# ERpcukBOx.net
KiCad netlist of a schematic drawn in EAGLE
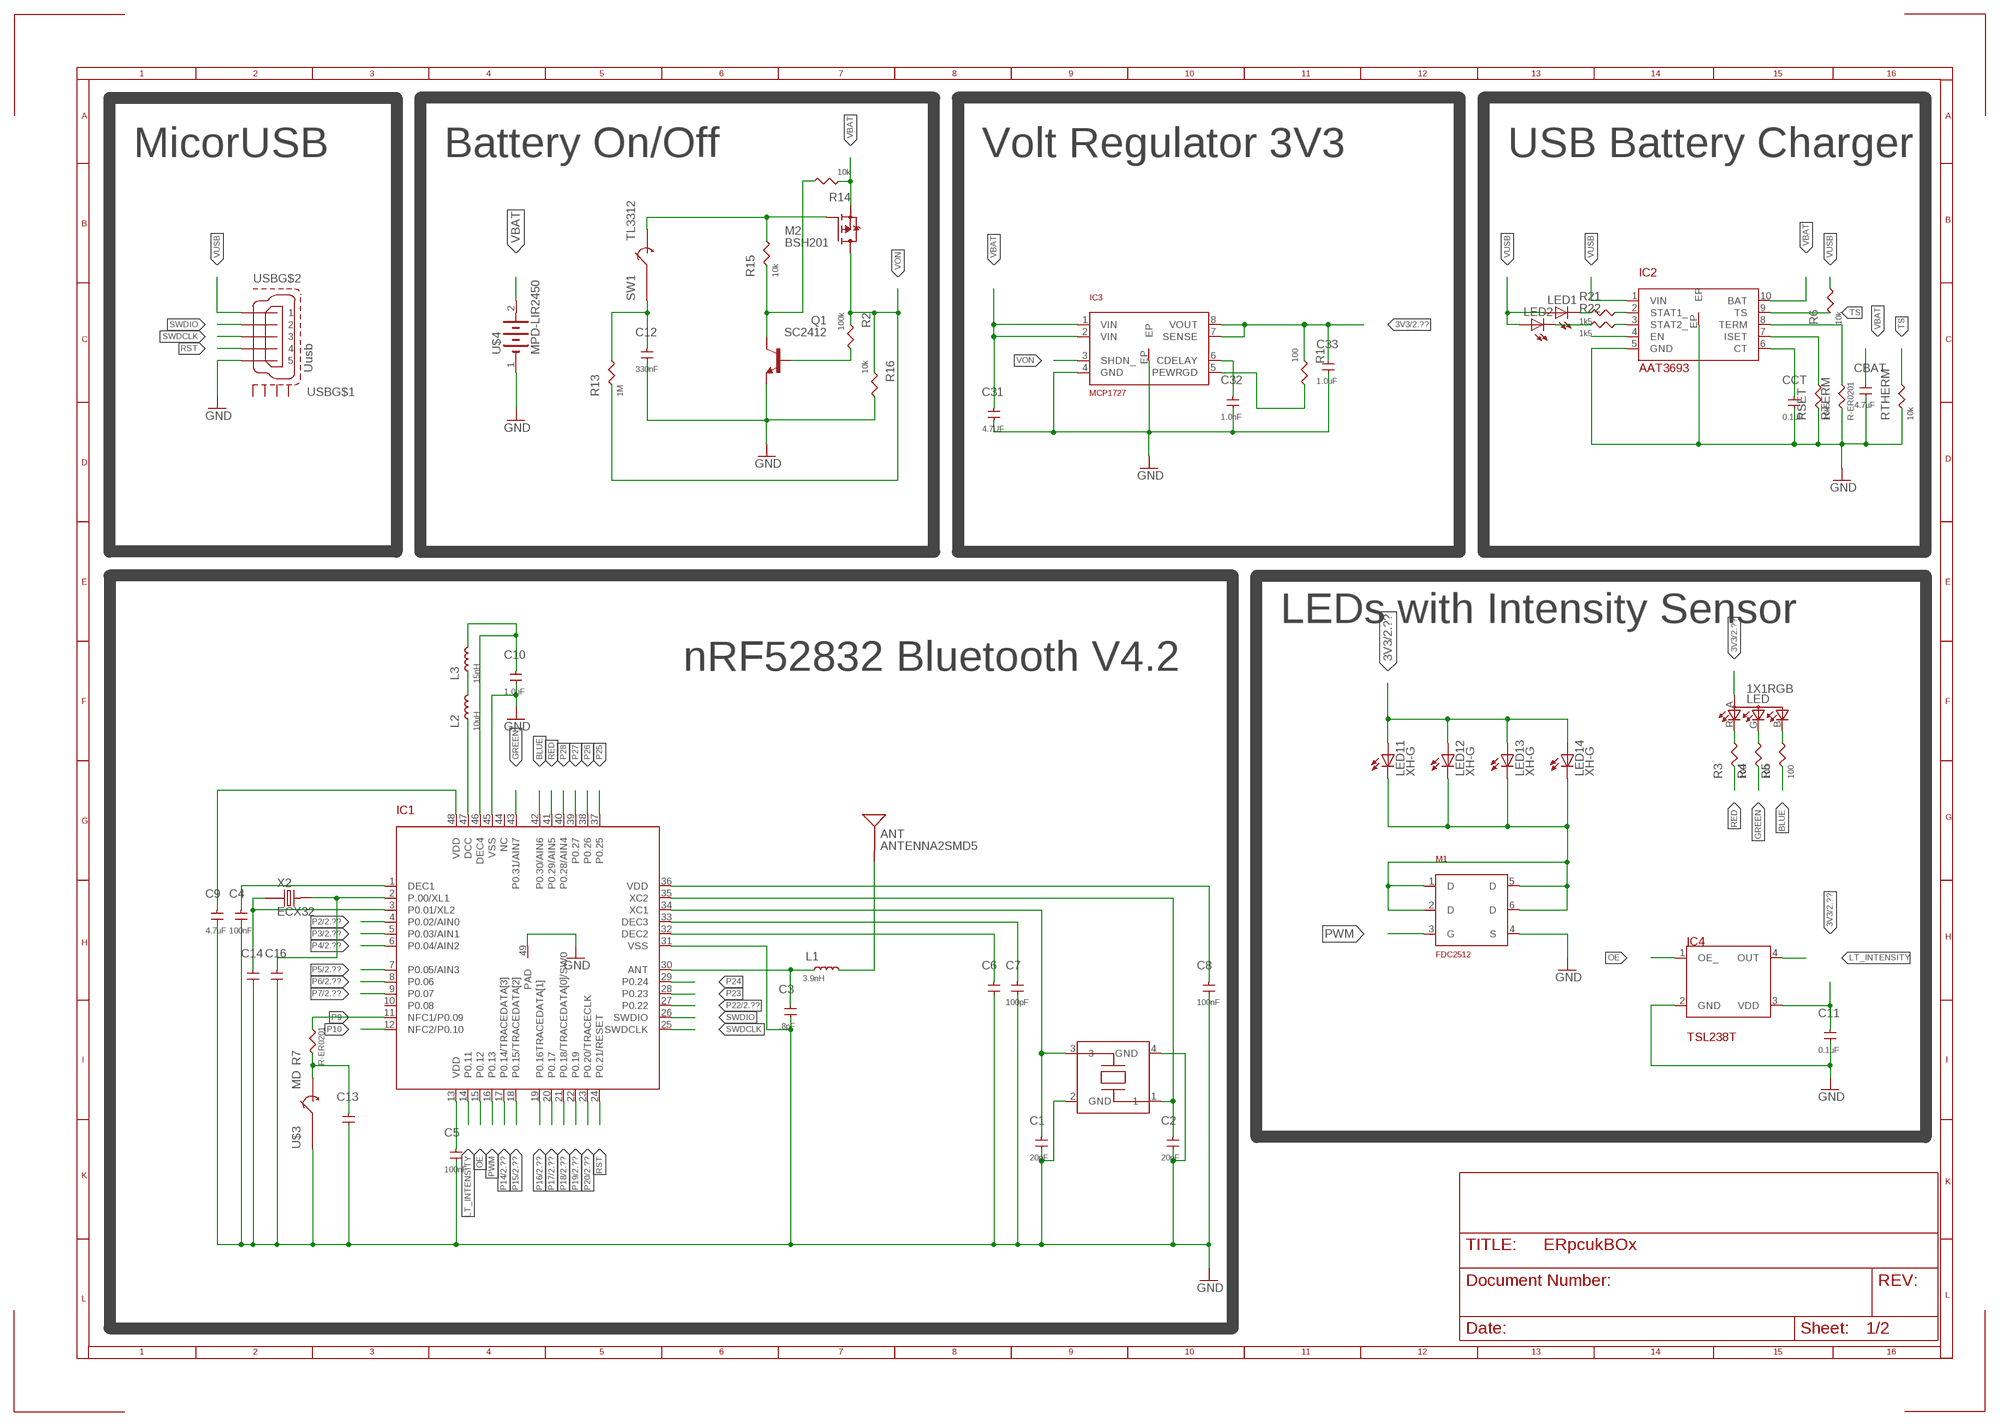
[diagram p0: schematic, sheet 1]
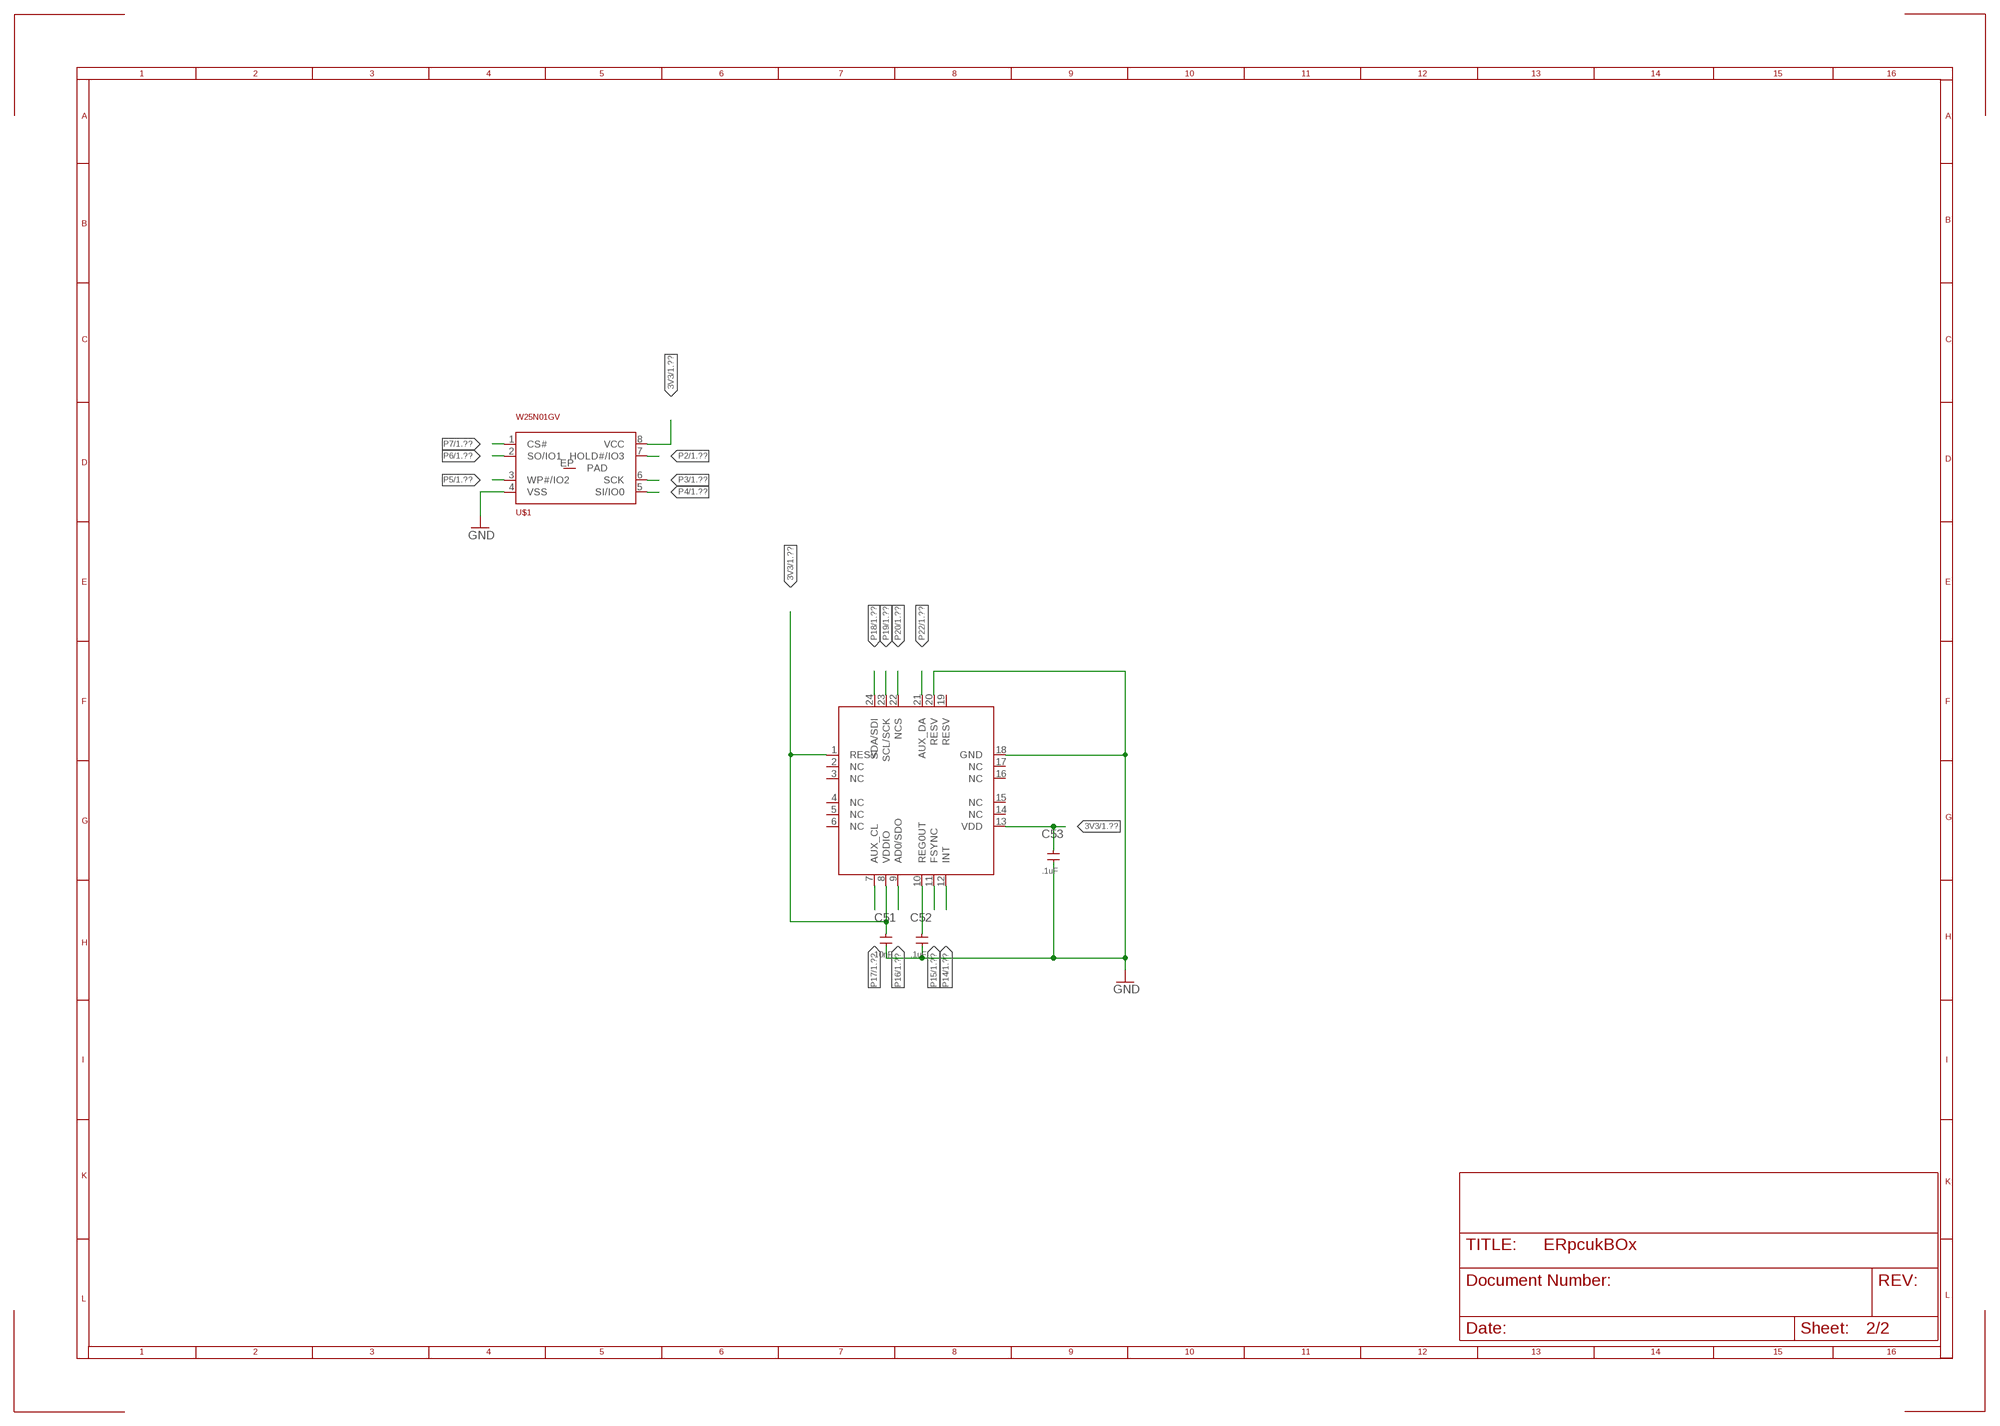
[diagram p1: schematic, sheet 2]

(export (version "E")
  (design (tool "Eeschema 10.0.6"))
  (components
    (comp (ref "C51")
      (value "10nF")
      (footprint "eagle-import:C0201")
      (libsource (lib "eagle-import") (part "C-ER201"))
    )
    (comp (ref "C52")
      (value ".1uF")
      (footprint "eagle-import:C0201")
      (libsource (lib "eagle-import") (part "C-ER201"))
    )
    (comp (ref "C53")
      (value ".1uF")
      (footprint "eagle-import:C0201")
      (libsource (lib "eagle-import") (part "C-ER201"))
    )
    (comp (ref "IC5")
      (value "MPU9250")
      (footprint "eagle-import:3X3_24_QFN_CORRECTED")
      (libsource (lib "eagle-import") (part "MPU9250_CORRECTED"))
    )
    (comp (ref "U$1")
      (value "W25N01GV")
      (footprint "eagle-import:8WSON6X8")
      (libsource (lib "eagle-import") (part "W25N01GV"))
    )
    (comp (ref "ANT")
      (value "ANTENNA2SMD5")
      (footprint "eagle-import:ANTENNA-CHIP5")
      (libsource (lib "eagle-import") (part "ANTENNA2SMD5"))
    )
    (comp (ref "C1")
      (value "20pF")
      (footprint "eagle-import:C0201")
      (libsource (lib "eagle-import") (part "C-ER201"))
    )
    (comp (ref "C2")
      (value "20pF")
      (footprint "eagle-import:C0201")
      (libsource (lib "eagle-import") (part "C-ER201"))
    )
    (comp (ref "C3")
      (value ".8pF")
      (footprint "eagle-import:C0201")
      (libsource (lib "eagle-import") (part "C-ER201"))
    )
    (comp (ref "C4")
      (value "100nF")
      (footprint "eagle-import:C0201")
      (libsource (lib "eagle-import") (part "C-ER201"))
    )
    (comp (ref "C5")
      (value "100nF")
      (footprint "eagle-import:C0201")
      (libsource (lib "eagle-import") (part "C-ER201"))
    )
    (comp (ref "C6")
      (value "C-ER201")
      (footprint "eagle-import:C0201")
      (libsource (lib "eagle-import") (part "C-ER201"))
    )
    (comp (ref "C7")
      (value "100pF")
      (footprint "eagle-import:C0201")
      (libsource (lib "eagle-import") (part "C-ER201"))
    )
    (comp (ref "C8")
      (value "100nF")
      (footprint "eagle-import:C0201")
      (libsource (lib "eagle-import") (part "C-ER201"))
    )
    (comp (ref "C9")
      (value "4.7uF")
      (footprint "eagle-import:C0402")
      (libsource (lib "eagle-import") (part "C-ERC0402"))
    )
    (comp (ref "C10")
      (value "1.0uF")
      (footprint "eagle-import:C0201")
      (libsource (lib "eagle-import") (part "C-ER201"))
    )
    (comp (ref "C11")
      (value "0.1uF")
      (footprint "eagle-import:C0201")
      (libsource (lib "eagle-import") (part "C-ER201"))
    )
    (comp (ref "C12")
      (value "330nF")
      (footprint "eagle-import:C0201")
      (libsource (lib "eagle-import") (part "C-ER201"))
    )
    (comp (ref "C13")
      (value "C-ER201")
      (footprint "eagle-import:C0201")
      (libsource (lib "eagle-import") (part "C-ER201"))
    )
    (comp (ref "C14")
      (value "C-ER201")
      (footprint "eagle-import:C0201")
      (libsource (lib "eagle-import") (part "C-ER201"))
    )
    (comp (ref "C16")
      (value "C-ER201")
      (footprint "eagle-import:C0201")
      (libsource (lib "eagle-import") (part "C-ER201"))
    )
    (comp (ref "C31")
      (value "4.7UF")
      (footprint "eagle-import:C0402")
      (libsource (lib "eagle-import") (part "C-ERC0402"))
    )
    (comp (ref "C32")
      (value "1.0nF")
      (footprint "eagle-import:C0201")
      (libsource (lib "eagle-import") (part "C-ER201"))
    )
    (comp (ref "C33")
      (value "1.0uF")
      (footprint "eagle-import:C0201")
      (libsource (lib "eagle-import") (part "C-ER201"))
    )
    (comp (ref "CBAT")
      (value "4.7uF")
      (footprint "eagle-import:C0402")
      (libsource (lib "eagle-import") (part "C-ERC0402"))
    )
    (comp (ref "CCT")
      (value "0.1uF")
      (footprint "eagle-import:C0201")
      (libsource (lib "eagle-import") (part "C-ER201"))
    )
    (comp (ref "IC1")
      (value "NRF52832")
      (footprint "eagle-import:QFN48")
      (libsource (lib "eagle-import") (part "NRF52832"))
    )
    (comp (ref "IC2")
      (value "AAT3693")
      (footprint "eagle-import:AAT3693")
      (libsource (lib "eagle-import") (part "AAT3693"))
    )
    (comp (ref "IC3")
      (value "MCP1727")
      (footprint "eagle-import:DFN8-3X3")
      (libsource (lib "eagle-import") (part "MCP1727"))
    )
    (comp (ref "IC4")
      (value "TSL238T")
      (footprint "eagle-import:T4")
      (libsource (lib "eagle-import") (part "TSL238T"))
    )
    (comp (ref "L1")
      (value "3.9nH")
      (footprint "eagle-import:C0201")
      (libsource (lib "eagle-import") (part "L-ER0201"))
    )
    (comp (ref "L2")
      (value "10uH")
      (footprint "eagle-import:R0603")
      (libsource (lib "eagle-import") (part "L-ERL603"))
    )
    (comp (ref "L3")
      (value "15nH")
      (footprint "eagle-import:C0201")
      (libsource (lib "eagle-import") (part "L-ER0201"))
    )
    (comp (ref "LED")
      (value "1X1RGB")
      (footprint "eagle-import:1X1")
      (libsource (lib "eagle-import") (part "1X1RGB"))
    )
    (comp (ref "LED1")
      (value "LEDCHIP-LED0603")
      (footprint "eagle-import:CHIP-LED0603")
      (libsource (lib "eagle-import") (part "LEDCHIP-LED0603"))
    )
    (comp (ref "LED2")
      (value "LEDCHIP-LED0603")
      (footprint "eagle-import:CHIP-LED0603")
      (libsource (lib "eagle-import") (part "LEDCHIP-LED0603"))
    )
    (comp (ref "LED11")
      (value "XH-G")
      (footprint "eagle-import:XH-G")
      (libsource (lib "eagle-import") (part "XH-G"))
    )
    (comp (ref "LED12")
      (value "XH-G")
      (footprint "eagle-import:XH-G")
      (libsource (lib "eagle-import") (part "XH-G"))
    )
    (comp (ref "LED13")
      (value "XH-G")
      (footprint "eagle-import:XH-G")
      (libsource (lib "eagle-import") (part "XH-G"))
    )
    (comp (ref "LED14")
      (value "XH-G")
      (footprint "eagle-import:XH-G")
      (libsource (lib "eagle-import") (part "XH-G"))
    )
    (comp (ref "M1")
      (value "FDC2512")
      (footprint "eagle-import:SSOT6")
      (libsource (lib "eagle-import") (part "FDC2512"))
    )
    (comp (ref "M2")
      (value "BSH201")
      (footprint "eagle-import:SOT23")
      (libsource (lib "eagle-import") (part "BSH201"))
    )
    (comp (ref "Q1")
      (value "SC2412")
      (footprint "eagle-import:SC59-BEC")
      (libsource (lib "eagle-import") (part "SC2412"))
    )
    (comp (ref "R1")
      (value "100")
      (footprint "eagle-import:R0201")
      (libsource (lib "eagle-import") (part "R-ER0201"))
    )
    (comp (ref "R2")
      (value "100k")
      (footprint "eagle-import:R0201")
      (libsource (lib "eagle-import") (part "R-ER0201"))
    )
    (comp (ref "R3")
      (value "100")
      (footprint "eagle-import:R0201")
      (libsource (lib "eagle-import") (part "R-ER0201"))
    )
    (comp (ref "R4")
      (value "100")
      (footprint "eagle-import:R0201")
      (libsource (lib "eagle-import") (part "R-ER0201"))
    )
    (comp (ref "R5")
      (value "100")
      (footprint "eagle-import:R0201")
      (libsource (lib "eagle-import") (part "R-ER0201"))
    )
    (comp (ref "R6")
      (value "10k")
      (footprint "eagle-import:R0201")
      (libsource (lib "eagle-import") (part "R-ER0201"))
    )
    (comp (ref "R7")
      (value "R-ER0201")
      (footprint "eagle-import:R0201")
      (libsource (lib "eagle-import") (part "R-ER0201"))
    )
    (comp (ref "R13")
      (value "1M")
      (footprint "eagle-import:R0201")
      (libsource (lib "eagle-import") (part "R-ER0201"))
    )
    (comp (ref "R14")
      (value "10k")
      (footprint "eagle-import:R0201")
      (libsource (lib "eagle-import") (part "R-ER0201"))
    )
    (comp (ref "R15")
      (value "10k")
      (footprint "eagle-import:R0201")
      (libsource (lib "eagle-import") (part "R-ER0201"))
    )
    (comp (ref "R16")
      (value "10k")
      (footprint "eagle-import:R0201")
      (libsource (lib "eagle-import") (part "R-ER0201"))
    )
    (comp (ref "R21")
      (value "1k5")
      (footprint "eagle-import:R0201")
      (libsource (lib "eagle-import") (part "R-ER0201"))
    )
    (comp (ref "R22")
      (value "1k5")
      (footprint "eagle-import:R0201")
      (libsource (lib "eagle-import") (part "R-ER0201"))
    )
    (comp (ref "RSET")
      (value "16k5")
      (footprint "eagle-import:R0201")
      (libsource (lib "eagle-import") (part "R-ER0201"))
    )
    (comp (ref "RTERM")
      (value "R-ER0201")
      (footprint "eagle-import:R0201")
      (libsource (lib "eagle-import") (part "R-ER0201"))
    )
    (comp (ref "RTHERM")
      (value "10k")
      (footprint "eagle-import:R0201")
      (libsource (lib "eagle-import") (part "R-ER0201"))
    )
    (comp (ref "SW1")
      (value "TL3312")
      (footprint "eagle-import:TL3312")
      (libsource (lib "eagle-import") (part "TL3312"))
    )
    (comp (ref "U$3") (value "MD") (footprint "eagle-import:MD") (libsource (lib "eagle-import") (part "MD")))
    (comp (ref "U$4")
      (value "MPD-LIR2450")
      (footprint "eagle-import:LIR2450")
      (libsource (lib "eagle-import") (part "MPD-LIR2450"))
    )
    (comp (ref "USB")
      (value "Uusb")
      (footprint "eagle-import:ZX62R-B-5P")
      (libsource (lib "eagle-import") (part "MICRO-USB-SHIELD-ZX62R-B-5P"))
    )
    (comp (ref "X1")
      (value "FA-128")
      (footprint "eagle-import:FA-128")
      (libsource (lib "eagle-import") (part "FA-128"))
    )
    (comp (ref "X2")
      (value "ECX32")
      (footprint "eagle-import:ECX39")
      (libsource (lib "eagle-import") (part "ECX32"))
    )
  )
  (nets
    (net (code "1") (name "3V3") (class "Default")
      (node (ref "C11") (pin "2") (pinfunction "P$2_2") (pintype "bidirectional"))
      (node (ref "C33") (pin "2") (pinfunction "P$2_2") (pintype "bidirectional"))
      (node (ref "C5") (pin "2") (pinfunction "P$2_2") (pintype "bidirectional"))
      (node (ref "C51") (pin "2") (pinfunction "P$2_2") (pintype "bidirectional"))
      (node (ref "C53") (pin "2") (pinfunction "P$2_2") (pintype "bidirectional"))
      (node (ref "C8") (pin "2") (pinfunction "P$2_2") (pintype "bidirectional"))
      (node (ref "C9") (pin "2") (pinfunction "P$2_2") (pintype "bidirectional"))
      (node (ref "IC1") (pin "13") (pinfunction "VDD_13") (pintype "bidirectional"))
      (node (ref "IC1") (pin "36") (pinfunction "VDD_36") (pintype "bidirectional"))
      (node (ref "IC1") (pin "48") (pinfunction "VDD_48") (pintype "bidirectional"))
      (node (ref "IC3") (pin "7") (pinfunction "SENSE_7") (pintype "bidirectional"))
      (node (ref "IC3") (pin "8") (pinfunction "VOUT_8") (pintype "bidirectional"))
      (node (ref "IC4") (pin "3") (pinfunction "VDD_3") (pintype "bidirectional"))
      (node (ref "IC5") (pin "1") (pinfunction "RESV_1") (pintype "bidirectional"))
      (node (ref "IC5") (pin "13") (pinfunction "VDD_13") (pintype "bidirectional"))
      (node (ref "IC5") (pin "8") (pinfunction "VDDIO_8") (pintype "bidirectional"))
      (node (ref "LED") (pin "A") (pinfunction "A2_A") (pintype "passive"))
      (node (ref "LED11") (pin "2") (pinfunction "A_2") (pintype "passive"))
      (node (ref "LED12") (pin "2") (pinfunction "A_2") (pintype "passive"))
      (node (ref "LED13") (pin "2") (pinfunction "A_2") (pintype "passive"))
      (node (ref "LED14") (pin "2") (pinfunction "A_2") (pintype "passive"))
      (node (ref "R1") (pin "1") (pinfunction "P$1_1") (pintype "bidirectional"))
      (node (ref "U$1") (pin "8") (pinfunction "VCC_8") (pintype "bidirectional"))
    )
    (net (code "2") (name "BLUE") (class "Default")
      (node (ref "IC1") (pin "42") (pinfunction "P0.30/AIN6_42") (pintype "bidirectional"))
      (node (ref "R5") (pin "1") (pinfunction "P$1_1") (pintype "bidirectional"))
    )
    (net (code "3") (name "GND") (class "Default")
      (node (ref "C1") (pin "1") (pinfunction "P$1_1") (pintype "bidirectional"))
      (node (ref "C10") (pin "1") (pinfunction "P$1_1") (pintype "bidirectional"))
      (node (ref "C11") (pin "1") (pinfunction "P$1_1") (pintype "bidirectional"))
      (node (ref "C12") (pin "1") (pinfunction "P$1_1") (pintype "bidirectional"))
      (node (ref "C13") (pin "1") (pinfunction "P$1_1") (pintype "bidirectional"))
      (node (ref "C14") (pin "1") (pinfunction "P$1_1") (pintype "bidirectional"))
      (node (ref "C16") (pin "1") (pinfunction "P$1_1") (pintype "bidirectional"))
      (node (ref "C2") (pin "1") (pinfunction "P$1_1") (pintype "bidirectional"))
      (node (ref "C3") (pin "1") (pinfunction "P$1_1") (pintype "bidirectional"))
      (node (ref "C31") (pin "1") (pinfunction "P$1_1") (pintype "bidirectional"))
      (node (ref "C32") (pin "1") (pinfunction "P$1_1") (pintype "bidirectional"))
      (node (ref "C33") (pin "1") (pinfunction "P$1_1") (pintype "bidirectional"))
      (node (ref "C4") (pin "1") (pinfunction "P$1_1") (pintype "bidirectional"))
      (node (ref "C5") (pin "1") (pinfunction "P$1_1") (pintype "bidirectional"))
      (node (ref "C51") (pin "1") (pinfunction "P$1_1") (pintype "bidirectional"))
      (node (ref "C52") (pin "1") (pinfunction "P$1_1") (pintype "bidirectional"))
      (node (ref "C53") (pin "1") (pinfunction "P$1_1") (pintype "bidirectional"))
      (node (ref "C6") (pin "1") (pinfunction "P$1_1") (pintype "bidirectional"))
      (node (ref "C7") (pin "1") (pinfunction "P$1_1") (pintype "bidirectional"))
      (node (ref "C8") (pin "1") (pinfunction "P$1_1") (pintype "bidirectional"))
      (node (ref "C9") (pin "1") (pinfunction "P$1_1") (pintype "bidirectional"))
      (node (ref "CBAT") (pin "1") (pinfunction "P$1_1") (pintype "bidirectional"))
      (node (ref "CCT") (pin "1") (pinfunction "P$1_1") (pintype "bidirectional"))
      (node (ref "IC1") (pin "31") (pinfunction "VSS_31") (pintype "bidirectional"))
      (node (ref "IC1") (pin "45") (pinfunction "VSS_45") (pintype "bidirectional"))
      (node (ref "IC1") (pin "49") (pinfunction "PAD_49") (pintype "bidirectional"))
      (node (ref "IC2") (pin "5") (pinfunction "GND_5") (pintype "bidirectional"))
      (node (ref "IC2") (pin "EP") (pinfunction "EP_EP") (pintype "bidirectional"))
      (node (ref "IC3") (pin "4") (pinfunction "GND_4") (pintype "bidirectional"))
      (node (ref "IC3") (pin "EP") (pinfunction "EP_EP") (pintype "bidirectional"))
      (node (ref "IC4") (pin "2") (pinfunction "GND_2") (pintype "bidirectional"))
      (node (ref "IC5") (pin "18") (pinfunction "GND_18") (pintype "bidirectional"))
      (node (ref "IC5") (pin "20") (pinfunction "RESV_20") (pintype "bidirectional"))
      (node (ref "M1") (pin "4") (pinfunction "S_4") (pintype "bidirectional"))
      (node (ref "Q1") (pin "E") (pinfunction "E_E") (pintype "passive"))
      (node (ref "R16") (pin "2") (pinfunction "P$2_2") (pintype "bidirectional"))
      (node (ref "RSET") (pin "1") (pinfunction "P$1_1") (pintype "bidirectional"))
      (node (ref "RTERM") (pin "1") (pinfunction "P$1_1") (pintype "bidirectional"))
      (node (ref "RTHERM") (pin "1") (pinfunction "P$1_1") (pintype "bidirectional"))
      (node (ref "U$1") (pin "4") (pinfunction "VSS_4") (pintype "bidirectional"))
      (node (ref "U$3") (pin "P$1") (pinfunction "1_P$1") (pintype "bidirectional"))
      (node (ref "U$4") (pin "1") (pinfunction "-_1") (pintype "passive"))
      (node (ref "USB") (pin "1") (pinfunction "5_1") (pintype "input"))
      (node (ref "X1") (pin "2") (pinfunction "GND_2") (pintype "bidirectional"))
      (node (ref "X1") (pin "4") (pinfunction "GND_4") (pintype "bidirectional"))
    )
    (net (code "4") (name "GREEN") (class "Default")
      (node (ref "IC1") (pin "43") (pinfunction "P0.31/AIN7_43") (pintype "bidirectional"))
      (node (ref "R4") (pin "1") (pinfunction "P$1_1") (pintype "bidirectional"))
    )
    (net (code "5") (name "LT_INTENSITY") (class "Default")
      (node (ref "IC1") (pin "14") (pinfunction "P0.11_14") (pintype "bidirectional"))
      (node (ref "IC4") (pin "4") (pinfunction "OUT_4") (pintype "bidirectional"))
    )
    (net (code "6") (name "Net-(ANT-SIGNAL)") (class "Default")
      (node (ref "ANT") (pin "FEED") (pinfunction "SIGNAL_FEED") (pintype "bidirectional"))
      (node (ref "L1") (pin "2") (pinfunction "P$2_2") (pintype "bidirectional"))
    )
    (net (code "7") (name "Net-(C1-P$2)") (class "Default")
      (node (ref "C1") (pin "2") (pinfunction "P$2_2") (pintype "bidirectional"))
      (node (ref "IC1") (pin "34") (pinfunction "XC1_34") (pintype "bidirectional"))
      (node (ref "X1") (pin "3") (pinfunction "3_3") (pintype "bidirectional"))
    )
    (net (code "8") (name "Net-(C2-P$2)") (class "Default")
      (node (ref "C2") (pin "2") (pinfunction "P$2_2") (pintype "bidirectional"))
      (node (ref "IC1") (pin "35") (pinfunction "XC2_35") (pintype "bidirectional"))
      (node (ref "X1") (pin "1") (pinfunction "1_1") (pintype "bidirectional"))
    )
    (net (code "9") (name "Net-(C3-P$2)") (class "Default")
      (node (ref "C3") (pin "2") (pinfunction "P$2_2") (pintype "bidirectional"))
      (node (ref "IC1") (pin "30") (pinfunction "ANT_30") (pintype "bidirectional"))
      (node (ref "L1") (pin "1") (pinfunction "P$1_1") (pintype "bidirectional"))
    )
    (net (code "10") (name "Net-(C4-P$2)") (class "Default")
      (node (ref "C4") (pin "2") (pinfunction "P$2_2") (pintype "bidirectional"))
      (node (ref "IC1") (pin "1") (pinfunction "DEC1_1") (pintype "bidirectional"))
    )
    (net (code "11") (name "Net-(C6-P$2)") (class "Default")
      (node (ref "C6") (pin "2") (pinfunction "P$2_2") (pintype "bidirectional"))
      (node (ref "IC1") (pin "32") (pinfunction "DEC2_32") (pintype "bidirectional"))
    )
    (net (code "12") (name "Net-(C7-P$2)") (class "Default")
      (node (ref "C7") (pin "2") (pinfunction "P$2_2") (pintype "bidirectional"))
      (node (ref "IC1") (pin "33") (pinfunction "DEC3_33") (pintype "bidirectional"))
    )
    (net (code "13") (name "Net-(C10-P$2)") (class "Default")
      (node (ref "C10") (pin "2") (pinfunction "P$2_2") (pintype "bidirectional"))
      (node (ref "IC1") (pin "46") (pinfunction "DEC4_46") (pintype "bidirectional"))
      (node (ref "L3") (pin "2") (pinfunction "P$2_2") (pintype "bidirectional"))
    )
    (net (code "14") (name "Net-(C12-P$2)") (class "Default")
      (node (ref "C12") (pin "2") (pinfunction "P$2_2") (pintype "bidirectional"))
      (node (ref "R13") (pin "2") (pinfunction "P$2_2") (pintype "bidirectional"))
      (node (ref "SW1") (pin "1") (pinfunction "1_1") (pintype "bidirectional"))
    )
    (net (code "15") (name "Net-(C13-P$2)") (class "Default")
      (node (ref "C13") (pin "2") (pinfunction "P$2_2") (pintype "bidirectional"))
      (node (ref "R7") (pin "1") (pinfunction "P$1_1") (pintype "bidirectional"))
      (node (ref "U$3") (pin "P$2") (pinfunction "2_P$2") (pintype "bidirectional"))
    )
    (net (code "16") (name "Net-(C14-P$2)") (class "Default")
      (node (ref "C14") (pin "2") (pinfunction "P$2_2") (pintype "bidirectional"))
      (node (ref "IC1") (pin "3") (pinfunction "P0.01/XL2_3") (pintype "bidirectional"))
      (node (ref "X2") (pin "P$1") (pinfunction "1_P$1") (pintype "passive"))
    )
    (net (code "17") (name "Net-(C16-P$2)") (class "Default")
      (node (ref "C16") (pin "2") (pinfunction "P$2_2") (pintype "bidirectional"))
      (node (ref "IC1") (pin "2") (pinfunction "P.00/XL1_2") (pintype "bidirectional"))
      (node (ref "X2") (pin "P$2") (pinfunction "2_P$2") (pintype "passive"))
    )
    (net (code "18") (name "Net-(C32-P$2)") (class "Default")
      (node (ref "C32") (pin "2") (pinfunction "P$2_2") (pintype "bidirectional"))
      (node (ref "IC3") (pin "6") (pinfunction "CDELAY_6") (pintype "bidirectional"))
    )
    (net (code "19") (name "Net-(C52-P$2)") (class "Default")
      (node (ref "C52") (pin "2") (pinfunction "P$2_2") (pintype "bidirectional"))
      (node (ref "IC5") (pin "10") (pinfunction "REG0UT_10") (pintype "bidirectional"))
    )
    (net (code "20") (name "Net-(CCT-P$2)") (class "Default")
      (node (ref "CCT") (pin "2") (pinfunction "P$2_2") (pintype "bidirectional"))
      (node (ref "IC2") (pin "6") (pinfunction "CT_6") (pintype "bidirectional"))
    )
    (net (code "21") (name "Net-(IC1-DCC)") (class "Default")
      (node (ref "IC1") (pin "47") (pinfunction "DCC_47") (pintype "bidirectional"))
      (node (ref "L2") (pin "1") (pinfunction "P$1_1") (pintype "bidirectional"))
    )
    (net (code "22") (name "Net-(IC2-ISET)") (class "Default")
      (node (ref "IC2") (pin "7") (pinfunction "ISET_7") (pintype "bidirectional"))
      (node (ref "RSET") (pin "2") (pinfunction "P$2_2") (pintype "bidirectional"))
    )
    (net (code "23") (name "Net-(IC2-STAT1_)") (class "Default")
      (node (ref "IC2") (pin "2") (pinfunction "STAT1__2") (pintype "bidirectional"))
      (node (ref "R21") (pin "2") (pinfunction "P$2_2") (pintype "bidirectional"))
    )
    (net (code "24") (name "Net-(IC2-STAT2_)") (class "Default")
      (node (ref "IC2") (pin "3") (pinfunction "STAT2__3") (pintype "bidirectional"))
      (node (ref "R22") (pin "2") (pinfunction "P$2_2") (pintype "bidirectional"))
    )
    (net (code "25") (name "Net-(IC2-TERM)") (class "Default")
      (node (ref "IC2") (pin "8") (pinfunction "TERM_8") (pintype "bidirectional"))
      (node (ref "RTERM") (pin "2") (pinfunction "P$2_2") (pintype "bidirectional"))
    )
    (net (code "26") (name "Net-(IC3-PEWRGD)") (class "Default")
      (node (ref "IC3") (pin "5") (pinfunction "PEWRGD_5") (pintype "bidirectional"))
      (node (ref "R1") (pin "2") (pinfunction "P$2_2") (pintype "bidirectional"))
    )
    (net (code "27") (name "Net-(L2-P$2)") (class "Default")
      (node (ref "L2") (pin "2") (pinfunction "P$2_2") (pintype "bidirectional"))
      (node (ref "L3") (pin "1") (pinfunction "P$1_1") (pintype "bidirectional"))
    )
    (net (code "28") (name "Net-(LED-CBLUE)") (class "Default")
      (node (ref "LED") (pin "G") (pinfunction "CBLUE_G") (pintype "passive"))
      (node (ref "R4") (pin "2") (pinfunction "P$2_2") (pintype "bidirectional"))
    )
    (net (code "29") (name "Net-(LED-CGREEN)") (class "Default")
      (node (ref "LED") (pin "B") (pinfunction "CGREEN_B") (pintype "passive"))
      (node (ref "R5") (pin "2") (pinfunction "P$2_2") (pintype "bidirectional"))
    )
    (net (code "30") (name "Net-(LED-CRED)") (class "Default")
      (node (ref "LED") (pin "R") (pinfunction "CRED_R") (pintype "passive"))
      (node (ref "R3") (pin "2") (pinfunction "P$2_2") (pintype "bidirectional"))
    )
    (net (code "31") (name "Net-(LED11-C)") (class "Default")
      (node (ref "LED11") (pin "1") (pinfunction "C_1") (pintype "passive"))
      (node (ref "LED12") (pin "1") (pinfunction "C_1") (pintype "passive"))
      (node (ref "LED13") (pin "1") (pinfunction "C_1") (pintype "passive"))
      (node (ref "LED14") (pin "1") (pinfunction "C_1") (pintype "passive"))
      (node (ref "M1") (pin "1") (pinfunction "D_1") (pintype "bidirectional"))
      (node (ref "M1") (pin "2") (pinfunction "D_2") (pintype "bidirectional"))
      (node (ref "M1") (pin "5") (pinfunction "D_5") (pintype "bidirectional"))
      (node (ref "M1") (pin "6") (pinfunction "D_6") (pintype "bidirectional"))
    )
    (net (code "32") (name "Net-(M2-G)") (class "Default")
      (node (ref "M2") (pin "1") (pinfunction "G_1") (pintype "passive"))
      (node (ref "R15") (pin "2") (pinfunction "P$2_2") (pintype "bidirectional"))
      (node (ref "SW1") (pin "3") (pinfunction "2_3") (pintype "bidirectional"))
    )
    (net (code "33") (name "Net-(R2-P$2)") (class "Default")
      (node (ref "Q1") (pin "B") (pinfunction "B_B") (pintype "passive"))
      (node (ref "R2") (pin "2") (pinfunction "P$2_2") (pintype "bidirectional"))
    )
    (net (code "34") (name "Net-(R14-P$2)") (class "Default")
      (node (ref "Q1") (pin "C") (pinfunction "C_C") (pintype "passive"))
      (node (ref "R14") (pin "2") (pinfunction "P$2_2") (pintype "bidirectional"))
      (node (ref "R15") (pin "1") (pinfunction "P$1_1") (pintype "bidirectional"))
    )
    (net (code "35") (name "Net-(R21-P$1)") (class "Default")
      (node (ref "LED1") (pin "C") (pinfunction "C_C") (pintype "passive"))
      (node (ref "R21") (pin "1") (pinfunction "P$1_1") (pintype "bidirectional"))
    )
    (net (code "36") (name "Net-(R22-P$1)") (class "Default")
      (node (ref "LED2") (pin "C") (pinfunction "C_C") (pintype "passive"))
      (node (ref "R22") (pin "1") (pinfunction "P$1_1") (pintype "bidirectional"))
    )
    (net (code "37") (name "OE") (class "Default")
      (node (ref "IC1") (pin "15") (pinfunction "P0.12_15") (pintype "bidirectional"))
      (node (ref "IC4") (pin "1") (pinfunction "OE__1") (pintype "bidirectional"))
    )
    (net (code "38") (name "P2") (class "Default")
      (node (ref "IC1") (pin "4") (pinfunction "P0.02/AIN0_4") (pintype "bidirectional"))
      (node (ref "U$1") (pin "7") (pinfunction "HOLD#/IO3_7") (pintype "bidirectional"))
    )
    (net (code "39") (name "P3") (class "Default")
      (node (ref "IC1") (pin "5") (pinfunction "P0.03/AIN1_5") (pintype "bidirectional"))
      (node (ref "U$1") (pin "6") (pinfunction "SCK_6") (pintype "bidirectional"))
    )
    (net (code "40") (name "P4") (class "Default")
      (node (ref "IC1") (pin "6") (pinfunction "P0.04/AIN2_6") (pintype "bidirectional"))
      (node (ref "U$1") (pin "5") (pinfunction "SI/IO0_5") (pintype "bidirectional"))
    )
    (net (code "41") (name "P5") (class "Default")
      (node (ref "IC1") (pin "7") (pinfunction "P0.05/AIN3_7") (pintype "bidirectional"))
      (node (ref "U$1") (pin "3") (pinfunction "WP#/IO2_3") (pintype "bidirectional"))
    )
    (net (code "42") (name "P6") (class "Default")
      (node (ref "IC1") (pin "8") (pinfunction "P0.06_8") (pintype "bidirectional"))
      (node (ref "U$1") (pin "2") (pinfunction "SO/IO1_2") (pintype "bidirectional"))
    )
    (net (code "43") (name "P7") (class "Default")
      (node (ref "IC1") (pin "9") (pinfunction "P0.07_9") (pintype "bidirectional"))
      (node (ref "U$1") (pin "1") (pinfunction "CS#_1") (pintype "bidirectional"))
    )
    (net (code "44") (name "P9") (class "Default")
      (node (ref "IC1") (pin "11") (pinfunction "NFC1/P0.09_11") (pintype "bidirectional"))
      (node (ref "R7") (pin "2") (pinfunction "P$2_2") (pintype "bidirectional"))
    )
    (net (code "45") (name "P10") (class "Default")
      (node (ref "IC1") (pin "12") (pinfunction "NFC2/P0.10_12") (pintype "bidirectional"))
    )
    (net (code "46") (name "P14") (class "Default")
      (node (ref "IC1") (pin "17") (pinfunction "P0.14/TRACEDATA[3]_17") (pintype "bidirectional"))
      (node (ref "IC5") (pin "12") (pinfunction "INT_12") (pintype "bidirectional"))
    )
    (net (code "47") (name "P15") (class "Default")
      (node (ref "IC1") (pin "18") (pinfunction "P0.15/TRACEDATA[2]_18") (pintype "bidirectional"))
      (node (ref "IC5") (pin "11") (pinfunction "FSYNC_11") (pintype "bidirectional"))
    )
    (net (code "48") (name "P16") (class "Default")
      (node (ref "IC1") (pin "19") (pinfunction "P0.16TRACEDATA[1]_19") (pintype "bidirectional"))
      (node (ref "IC5") (pin "9") (pinfunction "AD0/SDO_9") (pintype "bidirectional"))
    )
    (net (code "49") (name "P17") (class "Default")
      (node (ref "IC1") (pin "20") (pinfunction "P0.17_20") (pintype "bidirectional"))
      (node (ref "IC5") (pin "7") (pinfunction "AUX_CL_7") (pintype "bidirectional"))
    )
    (net (code "50") (name "P18") (class "Default")
      (node (ref "IC1") (pin "21") (pinfunction "P0.18/TRACEDATA[0]/SW0_21") (pintype "bidirectional"))
      (node (ref "IC5") (pin "24") (pinfunction "SDA/SDI_24") (pintype "bidirectional"))
    )
    (net (code "51") (name "P19") (class "Default")
      (node (ref "IC1") (pin "22") (pinfunction "P0.19_22") (pintype "bidirectional"))
      (node (ref "IC5") (pin "23") (pinfunction "SCL/SCK_23") (pintype "bidirectional"))
    )
    (net (code "52") (name "P20") (class "Default")
      (node (ref "IC1") (pin "23") (pinfunction "P0.20/TRACECLK_23") (pintype "bidirectional"))
      (node (ref "IC5") (pin "22") (pinfunction "NCS_22") (pintype "bidirectional"))
    )
    (net (code "53") (name "P22") (class "Default")
      (node (ref "IC1") (pin "27") (pinfunction "P0.22_27") (pintype "bidirectional"))
      (node (ref "IC5") (pin "21") (pinfunction "AUX_DA_21") (pintype "bidirectional"))
    )
    (net (code "54") (name "P23") (class "Default")
      (node (ref "IC1") (pin "28") (pinfunction "P0.23_28") (pintype "bidirectional"))
    )
    (net (code "55") (name "P24") (class "Default")
      (node (ref "IC1") (pin "29") (pinfunction "P0.24_29") (pintype "bidirectional"))
    )
    (net (code "56") (name "P25") (class "Default")
      (node (ref "IC1") (pin "37") (pinfunction "P0.25_37") (pintype "bidirectional"))
    )
    (net (code "57") (name "P26") (class "Default")
      (node (ref "IC1") (pin "38") (pinfunction "P0.26_38") (pintype "bidirectional"))
    )
    (net (code "58") (name "P27") (class "Default")
      (node (ref "IC1") (pin "39") (pinfunction "P0.27_39") (pintype "bidirectional"))
    )
    (net (code "59") (name "P28") (class "Default")
      (node (ref "IC1") (pin "40") (pinfunction "P0.28/AIN4_40") (pintype "bidirectional"))
    )
    (net (code "60") (name "PWM") (class "Default")
      (node (ref "IC1") (pin "16") (pinfunction "P0.13_16") (pintype "bidirectional"))
      (node (ref "M1") (pin "3") (pinfunction "G_3") (pintype "bidirectional"))
    )
    (net (code "61") (name "RED") (class "Default")
      (node (ref "IC1") (pin "41") (pinfunction "P0.29/AIN5_41") (pintype "bidirectional"))
      (node (ref "R3") (pin "1") (pinfunction "P$1_1") (pintype "bidirectional"))
    )
    (net (code "62") (name "RST") (class "Default")
      (node (ref "IC1") (pin "24") (pinfunction "P0.21/RESET_24") (pintype "bidirectional"))
      (node (ref "USB") (pin "2") (pinfunction "4_2") (pintype "input"))
    )
    (net (code "63") (name "SWDCLK") (class "Default")
      (node (ref "IC1") (pin "25") (pinfunction "SWDCLK_25") (pintype "bidirectional"))
      (node (ref "USB") (pin "3") (pinfunction "3_3") (pintype "input"))
    )
    (net (code "64") (name "SWDIO") (class "Default")
      (node (ref "IC1") (pin "26") (pinfunction "SWDIO_26") (pintype "bidirectional"))
      (node (ref "USB") (pin "4") (pinfunction "2_4") (pintype "input"))
    )
    (net (code "65") (name "TS") (class "Default")
      (node (ref "IC2") (pin "9") (pinfunction "TS_9") (pintype "bidirectional"))
      (node (ref "R6") (pin "1") (pinfunction "P$1_1") (pintype "bidirectional"))
      (node (ref "RTHERM") (pin "2") (pinfunction "P$2_2") (pintype "bidirectional"))
    )
    (net (code "66") (name "VBAT") (class "Default")
      (node (ref "C31") (pin "2") (pinfunction "P$2_2") (pintype "bidirectional"))
      (node (ref "CBAT") (pin "2") (pinfunction "P$2_2") (pintype "bidirectional"))
      (node (ref "IC2") (pin "10") (pinfunction "BAT_10") (pintype "bidirectional"))
      (node (ref "IC3") (pin "1") (pinfunction "VIN_1") (pintype "bidirectional"))
      (node (ref "IC3") (pin "2") (pinfunction "VIN_2") (pintype "bidirectional"))
      (node (ref "M2") (pin "2") (pinfunction "S_2") (pintype "passive"))
      (node (ref "R14") (pin "1") (pinfunction "P$1_1") (pintype "bidirectional"))
      (node (ref "U$4") (pin "2") (pinfunction "+_2") (pintype "passive"))
    )
    (net (code "67") (name "VON") (class "Default")
      (node (ref "IC3") (pin "3") (pinfunction "SHDN__3") (pintype "bidirectional"))
      (node (ref "M2") (pin "3") (pinfunction "D_3") (pintype "passive"))
      (node (ref "R13") (pin "1") (pinfunction "P$1_1") (pintype "bidirectional"))
      (node (ref "R16") (pin "1") (pinfunction "P$1_1") (pintype "bidirectional"))
      (node (ref "R2") (pin "1") (pinfunction "P$1_1") (pintype "bidirectional"))
    )
    (net (code "68") (name "VUSB") (class "Default")
      (node (ref "IC2") (pin "1") (pinfunction "VIN_1") (pintype "bidirectional"))
      (node (ref "IC2") (pin "4") (pinfunction "EN_4") (pintype "bidirectional"))
      (node (ref "LED1") (pin "A") (pinfunction "A_A") (pintype "passive"))
      (node (ref "LED2") (pin "A") (pinfunction "A_A") (pintype "passive"))
      (node (ref "R6") (pin "2") (pinfunction "P$2_2") (pintype "bidirectional"))
      (node (ref "USB") (pin "5") (pinfunction "1_5") (pintype "input"))
    )
    (net (code "69") (name "unconnected-(IC1-NC-Pad44)") (class "Default")
      (node (ref "IC1") (pin "44") (pinfunction "NC_44") (pintype "bidirectional"))
    )
    (net (code "70") (name "unconnected-(IC1-P0.08-Pad10)") (class "Default")
      (node (ref "IC1") (pin "10") (pinfunction "P0.08_10") (pintype "bidirectional"))
    )
    (net (code "71") (name "unconnected-(IC5-NC-Pad2)") (class "Default")
      (node (ref "IC5") (pin "2") (pinfunction "NC_2") (pintype "bidirectional"))
    )
    (net (code "72") (name "unconnected-(IC5-NC-Pad3)") (class "Default")
      (node (ref "IC5") (pin "3") (pinfunction "NC_3") (pintype "bidirectional"))
    )
    (net (code "73") (name "unconnected-(IC5-NC-Pad4)") (class "Default")
      (node (ref "IC5") (pin "4") (pinfunction "NC_4") (pintype "bidirectional"))
    )
    (net (code "74") (name "unconnected-(IC5-NC-Pad5)") (class "Default")
      (node (ref "IC5") (pin "5") (pinfunction "NC_5") (pintype "bidirectional"))
    )
    (net (code "75") (name "unconnected-(IC5-NC-Pad6)") (class "Default")
      (node (ref "IC5") (pin "6") (pinfunction "NC_6") (pintype "bidirectional"))
    )
    (net (code "76") (name "unconnected-(IC5-NC-Pad14)") (class "Default")
      (node (ref "IC5") (pin "14") (pinfunction "NC_14") (pintype "bidirectional"))
    )
    (net (code "77") (name "unconnected-(IC5-NC-Pad15)") (class "Default")
      (node (ref "IC5") (pin "15") (pinfunction "NC_15") (pintype "bidirectional"))
    )
    (net (code "78") (name "unconnected-(IC5-NC-Pad16)") (class "Default")
      (node (ref "IC5") (pin "16") (pinfunction "NC_16") (pintype "bidirectional"))
    )
    (net (code "79") (name "unconnected-(IC5-NC-Pad17)") (class "Default")
      (node (ref "IC5") (pin "17") (pinfunction "NC_17") (pintype "bidirectional"))
    )
    (net (code "80") (name "unconnected-(IC5-RESV-Pad19)") (class "Default")
      (node (ref "IC5") (pin "19") (pinfunction "RESV_19") (pintype "bidirectional"))
    )
    (net (code "81") (name "unconnected-(U$1-PAD-PadEP)") (class "Default")
      (node (ref "U$1") (pin "EP") (pinfunction "PAD_EP") (pintype "bidirectional"))
    )
    (net (code "82") (name "unconnected-(USBA-S1-PadM1)") (class "Default")
      (node (ref "USB") (pin "M1") (pinfunction "S1_M1") (pintype "passive"))
    )
    (net (code "83") (name "unconnected-(USBA-S2-PadM2)") (class "Default")
      (node (ref "USB") (pin "M2") (pinfunction "S2_M2") (pintype "passive"))
    )
    (net (code "84") (name "unconnected-(USBA-S3-PadM3)") (class "Default")
      (node (ref "USB") (pin "M3") (pinfunction "S3_M3") (pintype "passive"))
    )
    (net (code "85") (name "unconnected-(USBA-S4-PadM4)") (class "Default")
      (node (ref "USB") (pin "M4") (pinfunction "S4_M4") (pintype "passive"))
    )
  )
)
